# TFT_F1_2025-05-25_16-21-43.net
KiCad netlist of a schematic drawn in EasyEDA Pro
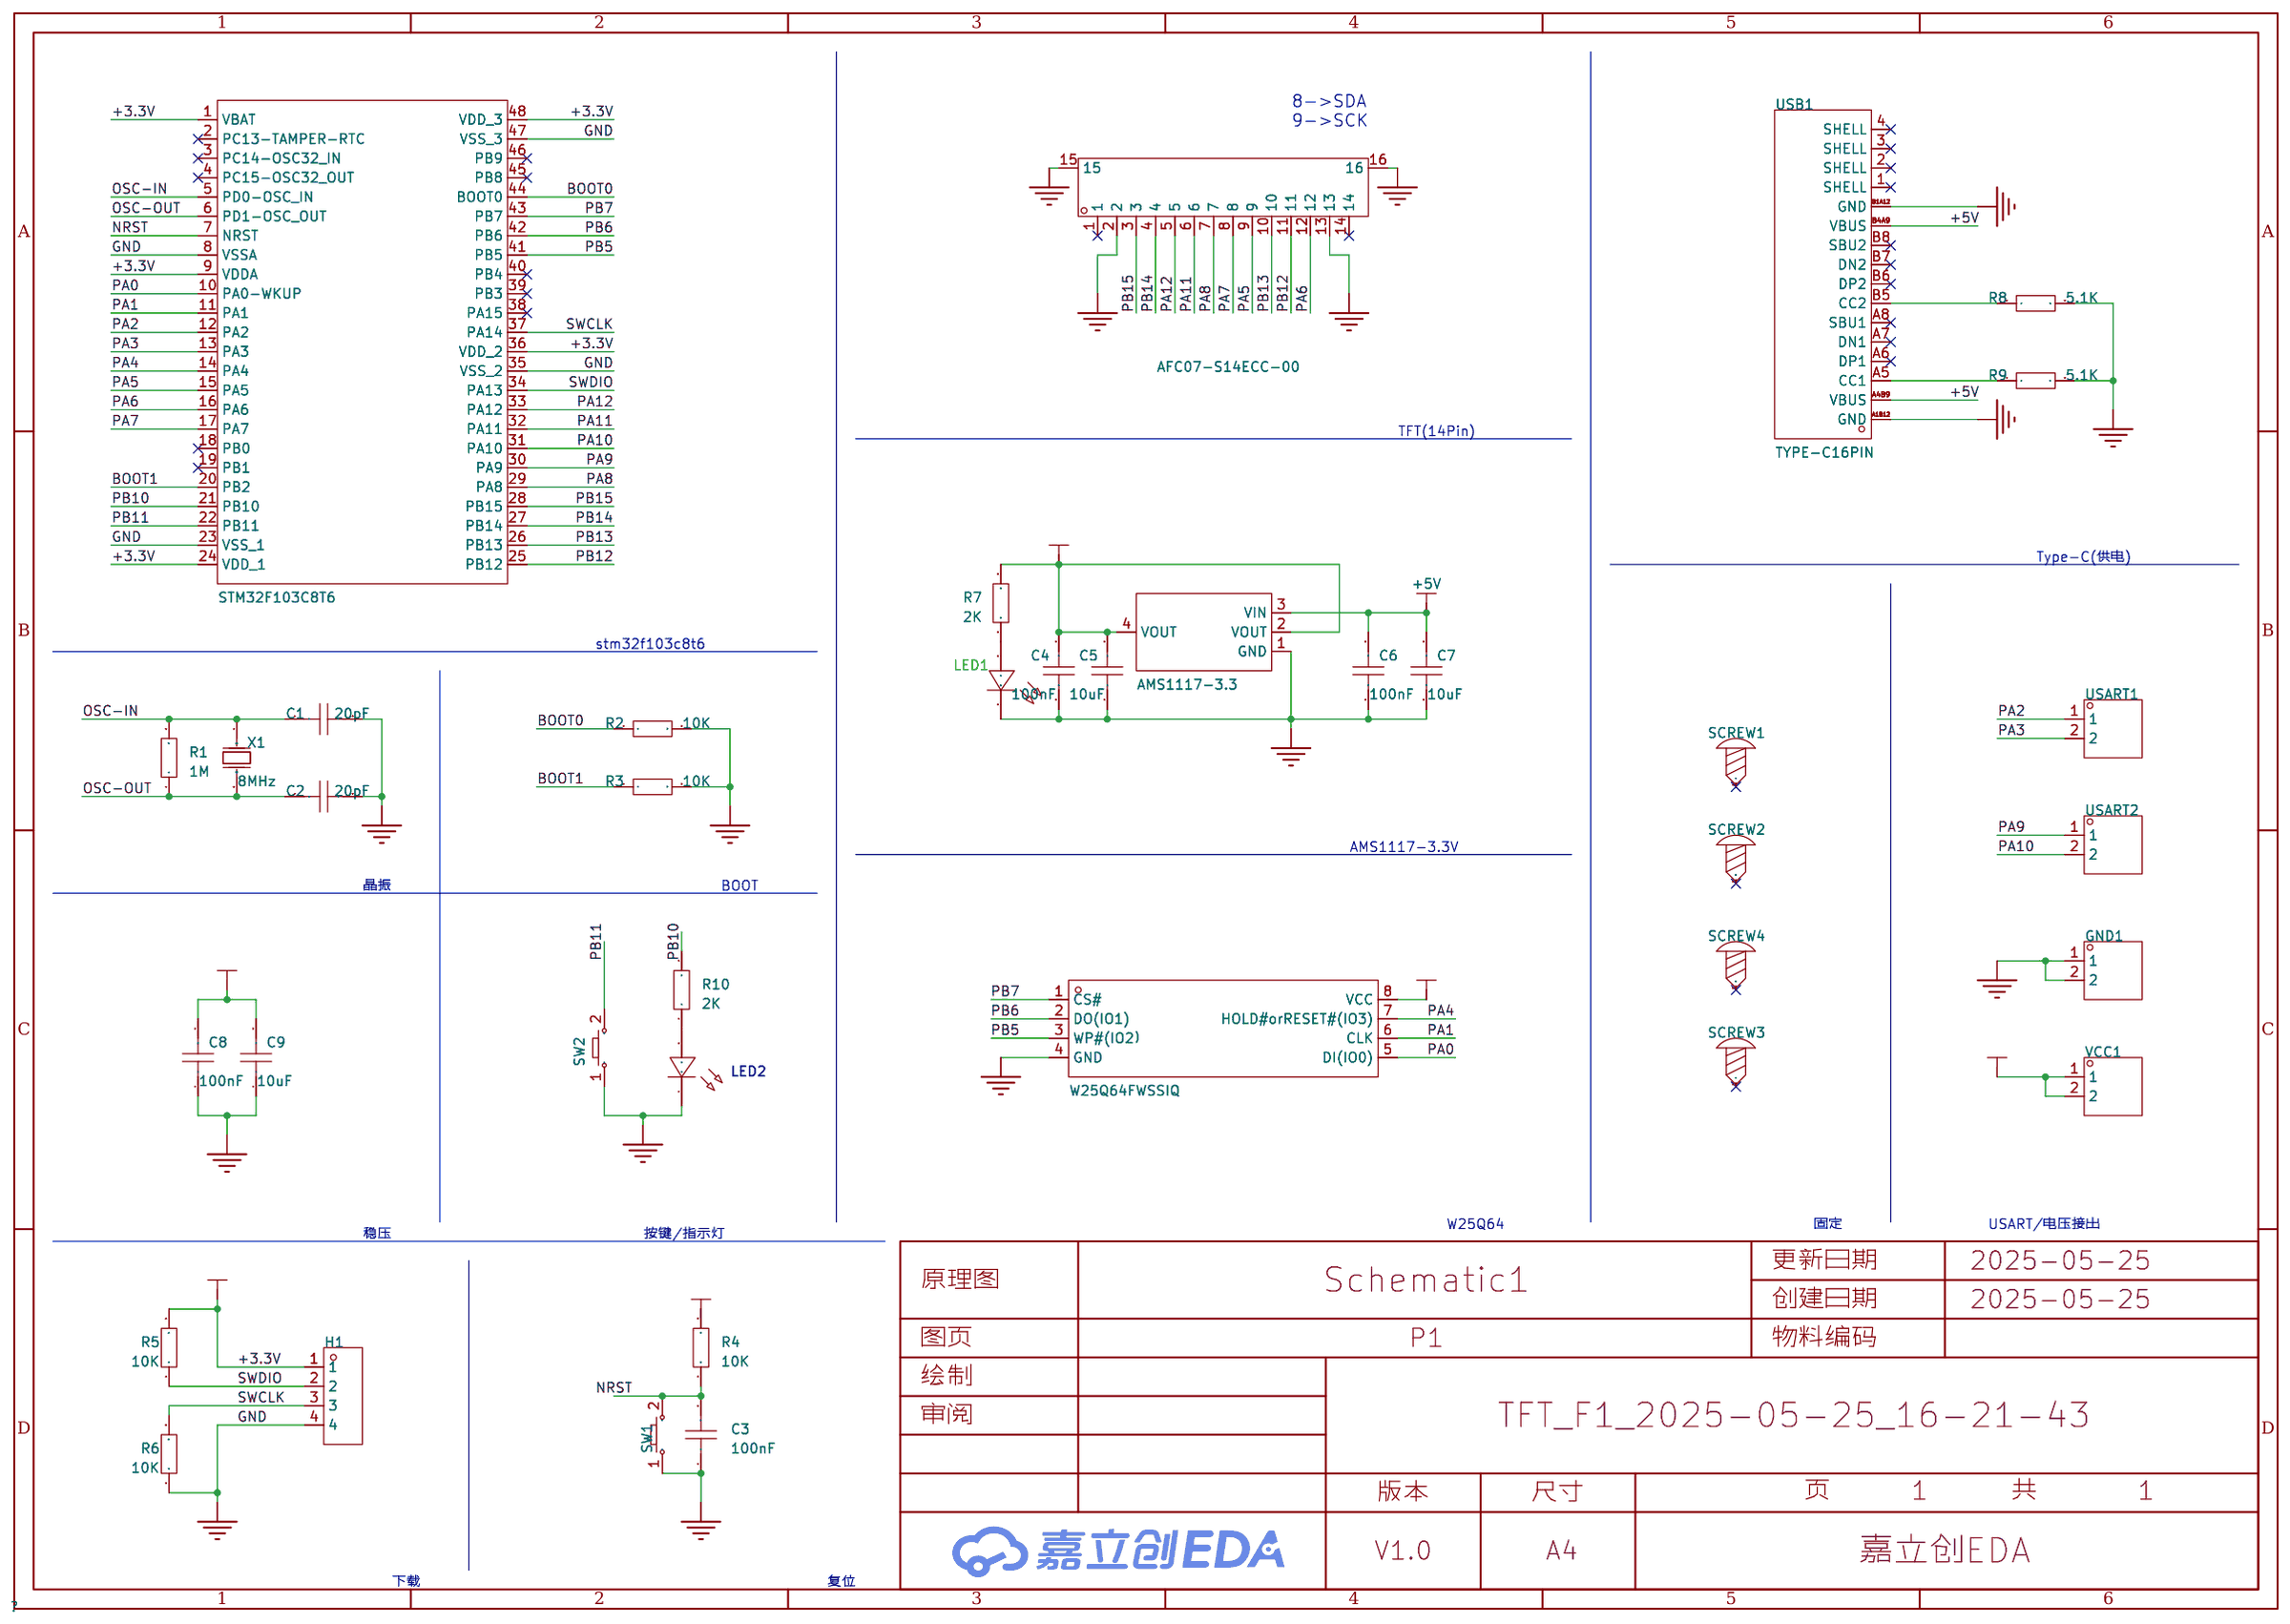
[diagram p0: schematic sheet]

(export (version "E")
  (design (tool "Eeschema 10.0.6"))
  (components
    (comp (ref "C1")
      (value "20pF")
      (footprint "easyedapro:C0805")
      (libsource (lib "easyedapro") (part "CapAcitance"))
    )
    (comp (ref "C2")
      (value "20pF")
      (footprint "easyedapro:C0805")
      (libsource (lib "easyedapro") (part "CapAcitance"))
    )
    (comp (ref "C3")
      (value "100nF")
      (footprint "easyedapro:C0805")
      (libsource (lib "easyedapro") (part "CapAcitance"))
    )
    (comp (ref "C4")
      (value "100nF")
      (footprint "easyedapro:C0805")
      (libsource (lib "easyedapro") (part "CapAcitance"))
    )
    (comp (ref "C5")
      (value "10uF")
      (footprint "easyedapro:C0805")
      (libsource (lib "easyedapro") (part "CapAcitance"))
    )
    (comp (ref "C6")
      (value "100nF")
      (footprint "easyedapro:C0805")
      (libsource (lib "easyedapro") (part "CapAcitance"))
    )
    (comp (ref "C7")
      (value "10uF")
      (footprint "easyedapro:C0805")
      (libsource (lib "easyedapro") (part "CapAcitance"))
    )
    (comp (ref "C8")
      (value "100nF")
      (footprint "easyedapro:C0805")
      (libsource (lib "easyedapro") (part "CapAcitance"))
    )
    (comp (ref "C9")
      (value "10uF")
      (footprint "easyedapro:C0805")
      (libsource (lib "easyedapro") (part "CapAcitance"))
    )
    (comp (ref "GND1")
      (value "~")
      (footprint "easyedapro:HDR-TH_2P-P2.54-V-M-1")
      (libsource (lib "easyedapro") (part "210S-1*2P L=11.6MMGold-plated black"))
    )
    (comp (ref "H1")
      (value "~")
      (footprint "easyedapro:HDR-TH_4P-P2.54-V-M")
      (libsource (lib "easyedapro") (part "PZ254V-11-04P"))
    )
    (comp (ref "LED1")
      (value "~")
      (footprint "easyedapro:LED_0805")
      (libsource (lib "easyedapro") (part "LED_G"))
    )
    (comp (ref "LED2")
      (value "~")
      (footprint "easyedapro:LED_0805")
      (libsource (lib "easyedapro") (part "LED_B"))
    )
    (comp (ref "P1")
      (value "AFC07-S14ECC-00")
      (footprint "easyedapro:FPC-SMD_14P-L12.5-W5.4-P0.50")
      (description "锁定特性:抽屉式;触点类型:上接;触点数量:14P;间距:0.5mm;安装类型:卧贴;")
      (fields (field (name "Manufacturer") "JS(钜硕电子)"))
      (libsource (lib "easyedapro") (part "FPC 0.5MM 14P Pull type H2.0mm Pick up"))
    )
    (comp (ref "R1") (value "1M") (footprint "easyedapro:R0805") (libsource (lib "easyedapro") (part "电阻")))
    (comp (ref "R2") (value "10K") (footprint "easyedapro:R0805") (libsource (lib "easyedapro") (part "电阻")))
    (comp (ref "R3") (value "10K") (footprint "easyedapro:R0805") (libsource (lib "easyedapro") (part "电阻")))
    (comp (ref "R4") (value "10K") (footprint "easyedapro:R0805") (libsource (lib "easyedapro") (part "电阻")))
    (comp (ref "R5") (value "10K") (footprint "easyedapro:R0805") (libsource (lib "easyedapro") (part "电阻")))
    (comp (ref "R6") (value "10K") (footprint "easyedapro:R0805") (libsource (lib "easyedapro") (part "电阻")))
    (comp (ref "R7") (value "2K") (footprint "easyedapro:R0805") (libsource (lib "easyedapro") (part "电阻")))
    (comp (ref "R8") (value "5.1K") (footprint "easyedapro:R0805") (libsource (lib "easyedapro") (part "电阻")))
    (comp (ref "R9") (value "5.1K") (footprint "easyedapro:R0805") (libsource (lib "easyedapro") (part "电阻")))
    (comp (ref "R10") (value "2K") (footprint "easyedapro:R0805") (libsource (lib "easyedapro") (part "电阻")))
    (comp (ref "SCREW1")
      (value "~")
      (footprint "easyedapro:M3螺丝")
      (libsource (lib "easyedapro") (part "螺丝孔"))
    )
    (comp (ref "SCREW2")
      (value "~")
      (footprint "easyedapro:M3螺丝")
      (libsource (lib "easyedapro") (part "螺丝孔"))
    )
    (comp (ref "SCREW3")
      (value "~")
      (footprint "easyedapro:M3螺丝")
      (libsource (lib "easyedapro") (part "螺丝孔"))
    )
    (comp (ref "SCREW4")
      (value "~")
      (footprint "easyedapro:M3螺丝")
      (libsource (lib "easyedapro") (part "螺丝孔"))
    )
    (comp (ref "SW1")
      (value "~")
      (footprint "easyedapro:Key_SMD_3x4x2")
      (libsource (lib "easyedapro") (part "轻触按键x2"))
    )
    (comp (ref "SW2")
      (value "~")
      (footprint "easyedapro:Key_SMD_3x4x2")
      (libsource (lib "easyedapro") (part "轻触按键x2"))
    )
    (comp (ref "U1")
      (value "STM32F103C8T6")
      (footprint "easyedapro:LQFP-48_L7.0-W7.0-P0.50-LS9.0-BL")
      (libsource (lib "easyedapro") (part "STM32F103C8T6_C9900100366"))
    )
    (comp (ref "U2")
      (value "AMS1117-3.3")
      (footprint "easyedapro:SOT-223-3_L6.5-W3.4-P2.30-LS7.0-BR")
      (description "输出类型:固定;工作电压:-;输出电压:3.3V;输出电流:1A;电源纹波抑制比(PSRR):72dB@(120Hz);输出极性:正极;")
      (fields (field (name "Manufacturer") "AMS"))
      (libsource (lib "easyedapro") (part "AMS1117-3.3"))
    )
    (comp (ref "U3")
      (value "W25Q64FWSSIQ")
      (footprint "easyedapro:SOIC-8_L5.3-W5.3-P1.27-LS8.0-BL")
      (fields (field (name "Manufacturer") "WINBOND(华邦)"))
      (libsource (lib "easyedapro") (part "W25Q64FWSSIQ"))
    )
    (comp (ref "USART1")
      (value "~")
      (footprint "easyedapro:HDR-TH_2P-P2.54-V-M-1")
      (libsource (lib "easyedapro") (part "210S-1*2P L=11.6MMGold-plated black"))
    )
    (comp (ref "USART2")
      (value "~")
      (footprint "easyedapro:HDR-TH_2P-P2.54-V-M-1")
      (libsource (lib "easyedapro") (part "210S-1*2P L=11.6MMGold-plated black"))
    )
    (comp (ref "USB1")
      (value "TYPE-C16PIN")
      (footprint "easyedapro:USB-C-SMD_TYPE-C16PIN")
      (description "连接器类型:Type-C;标准:USB 3.1;公母:母;安装方式:卧贴;触点数量:16P;端口数量:1;额定电流 - 电源:3A;工作温度范围:-40°C~+85°C;")
      (fields (field (name "Manufacturer") "SHOU HAN(首韩)"))
      (libsource (lib "easyedapro") (part "TYPE-C16PIN"))
    )
    (comp (ref "VCC1")
      (value "~")
      (footprint "easyedapro:HDR-TH_2P-P2.54-V-M-1")
      (libsource (lib "easyedapro") (part "210S-1*2P L=11.6MMGold-plated black"))
    )
    (comp (ref "X1")
      (value "8MHz")
      (footprint "easyedapro:CRYSTAL-SMD_L11.5-W4.8-LS12.7")
      (description "晶振类型:贴片晶振;频率:8MHz;常温频差:±20ppm;外接负载电容:20pF;频率稳定度(全温):±30ppm;")
      (fields (field (name "Manufacturer Part") "X49SM8MSD2SC") (field (name "Manufacturer") "YXC(扬兴晶振)"))
      (libsource (lib "easyedapro") (part "X49SM8MSD2SC"))
    )
  )
  (nets
    (net (code "1") (name "+3.3V") (class "Default")
      (node (ref "C4") (pin "2") (pinfunction "2_2") (pintype "input"))
      (node (ref "C5") (pin "2") (pinfunction "2_2") (pintype "input"))
      (node (ref "C8") (pin "2") (pinfunction "2_2") (pintype "input"))
      (node (ref "C9") (pin "2") (pinfunction "2_2") (pintype "input"))
      (node (ref "H1") (pin "1") (pinfunction "1_1") (pintype "unspecified"))
      (node (ref "R4") (pin "2") (pinfunction "2_2") (pintype "input"))
      (node (ref "R5") (pin "2") (pinfunction "2_2") (pintype "input"))
      (node (ref "R7") (pin "2") (pinfunction "2_2") (pintype "input"))
      (node (ref "U1") (pin "1") (pinfunction "VBAT_1") (pintype "unspecified"))
      (node (ref "U1") (pin "24") (pinfunction "VDD_1_24") (pintype "unspecified"))
      (node (ref "U1") (pin "36") (pinfunction "VDD_2_36") (pintype "unspecified"))
      (node (ref "U1") (pin "48") (pinfunction "VDD_3_48") (pintype "unspecified"))
      (node (ref "U1") (pin "9") (pinfunction "VDDA_9") (pintype "unspecified"))
      (node (ref "U2") (pin "2") (pinfunction "VOUT_2") (pintype "unspecified"))
      (node (ref "U2") (pin "4") (pinfunction "VOUT_4") (pintype "unspecified"))
      (node (ref "U3") (pin "8") (pinfunction "VCC_8") (pintype "unspecified"))
      (node (ref "VCC1") (pin "1") (pinfunction "1_1") (pintype "unspecified"))
      (node (ref "VCC1") (pin "2") (pinfunction "2_2") (pintype "unspecified"))
    )
    (net (code "2") (name "+5V") (class "Default")
      (node (ref "C6") (pin "2") (pinfunction "2_2") (pintype "input"))
      (node (ref "C7") (pin "2") (pinfunction "2_2") (pintype "input"))
      (node (ref "U2") (pin "3") (pinfunction "VIN_3") (pintype "unspecified"))
      (node (ref "USB1") (pin "A4B9") (pinfunction "VBUS_A4B9") (pintype "unspecified"))
      (node (ref "USB1") (pin "B4A9") (pinfunction "VBUS_B4A9") (pintype "unspecified"))
    )
    (net (code "3") (name "/BOOT0") (class "Default")
      (node (ref "R2") (pin "1") (pinfunction "1_1") (pintype "input"))
      (node (ref "U1") (pin "44") (pinfunction "BOOT0_44") (pintype "unspecified"))
    )
    (net (code "4") (name "/BOOT1") (class "Default")
      (node (ref "R3") (pin "1") (pinfunction "1_1") (pintype "input"))
      (node (ref "U1") (pin "20") (pinfunction "PB2_20") (pintype "unspecified"))
    )
    (net (code "5") (name "/NRST") (class "Default")
      (node (ref "C3") (pin "2") (pinfunction "2_2") (pintype "input"))
      (node (ref "R4") (pin "1") (pinfunction "1_1") (pintype "input"))
      (node (ref "SW1") (pin "2") (pinfunction "2_2") (pintype "input"))
      (node (ref "U1") (pin "7") (pinfunction "NRST_7") (pintype "unspecified"))
    )
    (net (code "6") (name "/OSC-IN") (class "Default")
      (node (ref "C1") (pin "1") (pinfunction "1_1") (pintype "input"))
      (node (ref "R1") (pin "2") (pinfunction "2_2") (pintype "input"))
      (node (ref "U1") (pin "5") (pinfunction "PD0-OSC_IN_5") (pintype "unspecified"))
      (node (ref "X1") (pin "1") (pinfunction "OSC1_1") (pintype "input"))
    )
    (net (code "7") (name "/OSC-OUT") (class "Default")
      (node (ref "C2") (pin "1") (pinfunction "1_1") (pintype "input"))
      (node (ref "R1") (pin "1") (pinfunction "1_1") (pintype "input"))
      (node (ref "U1") (pin "6") (pinfunction "PD1-OSC_OUT_6") (pintype "unspecified"))
      (node (ref "X1") (pin "2") (pinfunction "OSC2_2") (pintype "input"))
    )
    (net (code "8") (name "/PA0") (class "Default")
      (node (ref "U1") (pin "10") (pinfunction "PA0-WKUP_10") (pintype "unspecified"))
      (node (ref "U3") (pin "5") (pinfunction "DI(IO0)_5") (pintype "unspecified"))
    )
    (net (code "9") (name "/PA1") (class "Default")
      (node (ref "U1") (pin "11") (pinfunction "PA1_11") (pintype "unspecified"))
      (node (ref "U3") (pin "6") (pinfunction "CLK_6") (pintype "unspecified"))
    )
    (net (code "10") (name "/PA2") (class "Default")
      (node (ref "U1") (pin "12") (pinfunction "PA2_12") (pintype "unspecified"))
      (node (ref "USART1") (pin "1") (pinfunction "1_1") (pintype "unspecified"))
    )
    (net (code "11") (name "/PA3") (class "Default")
      (node (ref "U1") (pin "13") (pinfunction "PA3_13") (pintype "unspecified"))
      (node (ref "USART1") (pin "2") (pinfunction "2_2") (pintype "unspecified"))
    )
    (net (code "12") (name "/PA4") (class "Default")
      (node (ref "U1") (pin "14") (pinfunction "PA4_14") (pintype "unspecified"))
      (node (ref "U3") (pin "7") (pinfunction "HOLD#orRESET#(IO3)_7") (pintype "unspecified"))
    )
    (net (code "13") (name "/PA5") (class "Default")
      (node (ref "P1") (pin "9") (pinfunction "9_9") (pintype "unspecified"))
      (node (ref "U1") (pin "15") (pinfunction "PA5_15") (pintype "unspecified"))
    )
    (net (code "14") (name "/PA6") (class "Default")
      (node (ref "P1") (pin "12") (pinfunction "12_12") (pintype "unspecified"))
      (node (ref "U1") (pin "16") (pinfunction "PA6_16") (pintype "unspecified"))
    )
    (net (code "15") (name "/PA7") (class "Default")
      (node (ref "P1") (pin "8") (pinfunction "8_8") (pintype "unspecified"))
      (node (ref "U1") (pin "17") (pinfunction "PA7_17") (pintype "unspecified"))
    )
    (net (code "16") (name "/PA8") (class "Default")
      (node (ref "P1") (pin "7") (pinfunction "7_7") (pintype "unspecified"))
      (node (ref "U1") (pin "29") (pinfunction "PA8_29") (pintype "unspecified"))
    )
    (net (code "17") (name "/PA9") (class "Default")
      (node (ref "U1") (pin "30") (pinfunction "PA9_30") (pintype "unspecified"))
      (node (ref "USART2") (pin "1") (pinfunction "1_1") (pintype "unspecified"))
    )
    (net (code "18") (name "/PA10") (class "Default")
      (node (ref "U1") (pin "31") (pinfunction "PA10_31") (pintype "unspecified"))
      (node (ref "USART2") (pin "2") (pinfunction "2_2") (pintype "unspecified"))
    )
    (net (code "19") (name "/PA11") (class "Default")
      (node (ref "P1") (pin "6") (pinfunction "6_6") (pintype "unspecified"))
      (node (ref "U1") (pin "32") (pinfunction "PA11_32") (pintype "unspecified"))
    )
    (net (code "20") (name "/PA12") (class "Default")
      (node (ref "P1") (pin "5") (pinfunction "5_5") (pintype "unspecified"))
      (node (ref "U1") (pin "33") (pinfunction "PA12_33") (pintype "unspecified"))
    )
    (net (code "21") (name "/PB5") (class "Default")
      (node (ref "U1") (pin "41") (pinfunction "PB5_41") (pintype "unspecified"))
      (node (ref "U3") (pin "3") (pinfunction "WP#(IO2）_3") (pintype "unspecified"))
    )
    (net (code "22") (name "/PB6") (class "Default")
      (node (ref "U1") (pin "42") (pinfunction "PB6_42") (pintype "unspecified"))
      (node (ref "U3") (pin "2") (pinfunction "DO(IO1)_2") (pintype "unspecified"))
    )
    (net (code "23") (name "/PB7") (class "Default")
      (node (ref "U1") (pin "43") (pinfunction "PB7_43") (pintype "unspecified"))
      (node (ref "U3") (pin "1") (pinfunction "CS#_1") (pintype "unspecified"))
    )
    (net (code "24") (name "/PB10") (class "Default")
      (node (ref "R10") (pin "2") (pinfunction "2_2") (pintype "input"))
      (node (ref "U1") (pin "21") (pinfunction "PB10_21") (pintype "unspecified"))
    )
    (net (code "25") (name "/PB11") (class "Default")
      (node (ref "SW2") (pin "2") (pinfunction "2_2") (pintype "input"))
      (node (ref "U1") (pin "22") (pinfunction "PB11_22") (pintype "unspecified"))
    )
    (net (code "26") (name "/PB12") (class "Default")
      (node (ref "P1") (pin "11") (pinfunction "11_11") (pintype "unspecified"))
      (node (ref "U1") (pin "25") (pinfunction "PB12_25") (pintype "unspecified"))
    )
    (net (code "27") (name "/PB13") (class "Default")
      (node (ref "P1") (pin "10") (pinfunction "10_10") (pintype "unspecified"))
      (node (ref "U1") (pin "26") (pinfunction "PB13_26") (pintype "unspecified"))
    )
    (net (code "28") (name "/PB14") (class "Default")
      (node (ref "P1") (pin "4") (pinfunction "4_4") (pintype "unspecified"))
      (node (ref "U1") (pin "27") (pinfunction "PB14_27") (pintype "unspecified"))
    )
    (net (code "29") (name "/PB15") (class "Default")
      (node (ref "P1") (pin "3") (pinfunction "3_3") (pintype "unspecified"))
      (node (ref "U1") (pin "28") (pinfunction "PB15_28") (pintype "unspecified"))
    )
    (net (code "30") (name "/SWCLK") (class "Default")
      (node (ref "H1") (pin "3") (pinfunction "3_3") (pintype "unspecified"))
      (node (ref "R6") (pin "2") (pinfunction "2_2") (pintype "input"))
      (node (ref "U1") (pin "37") (pinfunction "PA14_37") (pintype "unspecified"))
    )
    (net (code "31") (name "/SWDIO") (class "Default")
      (node (ref "H1") (pin "2") (pinfunction "2_2") (pintype "unspecified"))
      (node (ref "R5") (pin "1") (pinfunction "1_1") (pintype "input"))
      (node (ref "U1") (pin "34") (pinfunction "PA13_34") (pintype "unspecified"))
    )
    (net (code "32") (name "GND") (class "Default")
      (node (ref "C1") (pin "2") (pinfunction "2_2") (pintype "input"))
      (node (ref "C2") (pin "2") (pinfunction "2_2") (pintype "input"))
      (node (ref "C3") (pin "1") (pinfunction "1_1") (pintype "input"))
      (node (ref "C4") (pin "1") (pinfunction "1_1") (pintype "input"))
      (node (ref "C5") (pin "1") (pinfunction "1_1") (pintype "input"))
      (node (ref "C6") (pin "1") (pinfunction "1_1") (pintype "input"))
      (node (ref "C7") (pin "1") (pinfunction "1_1") (pintype "input"))
      (node (ref "C8") (pin "1") (pinfunction "1_1") (pintype "input"))
      (node (ref "C9") (pin "1") (pinfunction "1_1") (pintype "input"))
      (node (ref "GND1") (pin "1") (pinfunction "1_1") (pintype "unspecified"))
      (node (ref "GND1") (pin "2") (pinfunction "2_2") (pintype "unspecified"))
      (node (ref "H1") (pin "4") (pinfunction "4_4") (pintype "unspecified"))
      (node (ref "LED1") (pin "1") (pinfunction "C_1") (pintype "input"))
      (node (ref "LED2") (pin "1") (pinfunction "C_1") (pintype "input"))
      (node (ref "P1") (pin "13") (pinfunction "13_13") (pintype "unspecified"))
      (node (ref "P1") (pin "15") (pinfunction "15_15") (pintype "unspecified"))
      (node (ref "P1") (pin "16") (pinfunction "16_16") (pintype "unspecified"))
      (node (ref "P1") (pin "2") (pinfunction "2_2") (pintype "unspecified"))
      (node (ref "R2") (pin "2") (pinfunction "2_2") (pintype "input"))
      (node (ref "R3") (pin "2") (pinfunction "2_2") (pintype "input"))
      (node (ref "R6") (pin "1") (pinfunction "1_1") (pintype "input"))
      (node (ref "R8") (pin "2") (pinfunction "2_2") (pintype "input"))
      (node (ref "R9") (pin "2") (pinfunction "2_2") (pintype "input"))
      (node (ref "SW1") (pin "1") (pinfunction "1_1") (pintype "input"))
      (node (ref "SW2") (pin "1") (pinfunction "1_1") (pintype "input"))
      (node (ref "U1") (pin "23") (pinfunction "VSS_1_23") (pintype "unspecified"))
      (node (ref "U1") (pin "35") (pinfunction "VSS_2_35") (pintype "unspecified"))
      (node (ref "U1") (pin "47") (pinfunction "VSS_3_47") (pintype "unspecified"))
      (node (ref "U1") (pin "8") (pinfunction "VSSA_8") (pintype "unspecified"))
      (node (ref "U2") (pin "1") (pinfunction "GND_1") (pintype "unspecified"))
      (node (ref "U3") (pin "4") (pinfunction "GND_4") (pintype "unspecified"))
      (node (ref "USB1") (pin "A1B12") (pinfunction "GND_A1B12") (pintype "unspecified"))
      (node (ref "USB1") (pin "B1A12") (pinfunction "GND_B1A12") (pintype "unspecified"))
    )
    (net (code "33") (name "Net-(LED1-A)") (class "Default")
      (node (ref "LED1") (pin "2") (pinfunction "A_2") (pintype "input"))
      (node (ref "R7") (pin "1") (pinfunction "1_1") (pintype "input"))
    )
    (net (code "34") (name "Net-(LED2-A)") (class "Default")
      (node (ref "LED2") (pin "2") (pinfunction "A_2") (pintype "input"))
      (node (ref "R10") (pin "1") (pinfunction "1_1") (pintype "input"))
    )
    (net (code "35") (name "Net-(USB1-CC1)") (class "Default")
      (node (ref "R9") (pin "1") (pinfunction "1_1") (pintype "input"))
      (node (ref "USB1") (pin "A5") (pinfunction "CC1_A5") (pintype "unspecified"))
    )
    (net (code "36") (name "Net-(USB1-CC2)") (class "Default")
      (node (ref "R8") (pin "1") (pinfunction "1_1") (pintype "input"))
      (node (ref "USB1") (pin "B5") (pinfunction "CC2_B5") (pintype "unspecified"))
    )
    (net (code "37") (name "unconnected-(P1-Pad1)") (class "Default")
      (node (ref "P1") (pin "1") (pinfunction "1_1") (pintype "unspecified+no_connect"))
    )
    (net (code "38") (name "unconnected-(P1-Pad14)") (class "Default")
      (node (ref "P1") (pin "14") (pinfunction "14_14") (pintype "unspecified+no_connect"))
    )
    (net (code "39") (name "unconnected-(SCREW1-Pad1)") (class "Default")
      (node (ref "SCREW1") (pin "1") (pinfunction "1_1") (pintype "input+no_connect"))
    )
    (net (code "40") (name "unconnected-(SCREW2-Pad1)") (class "Default")
      (node (ref "SCREW2") (pin "1") (pinfunction "1_1") (pintype "input+no_connect"))
    )
    (net (code "41") (name "unconnected-(SCREW3-Pad1)") (class "Default")
      (node (ref "SCREW3") (pin "1") (pinfunction "1_1") (pintype "input+no_connect"))
    )
    (net (code "42") (name "unconnected-(SCREW4-Pad1)") (class "Default")
      (node (ref "SCREW4") (pin "1") (pinfunction "1_1") (pintype "input+no_connect"))
    )
    (net (code "43") (name "unconnected-(U1-PA15-Pad38)") (class "Default")
      (node (ref "U1") (pin "38") (pinfunction "PA15_38") (pintype "unspecified+no_connect"))
    )
    (net (code "44") (name "unconnected-(U1-PB0-Pad18)") (class "Default")
      (node (ref "U1") (pin "18") (pinfunction "PB0_18") (pintype "unspecified+no_connect"))
    )
    (net (code "45") (name "unconnected-(U1-PB1-Pad19)") (class "Default")
      (node (ref "U1") (pin "19") (pinfunction "PB1_19") (pintype "unspecified+no_connect"))
    )
    (net (code "46") (name "unconnected-(U1-PB3-Pad39)") (class "Default")
      (node (ref "U1") (pin "39") (pinfunction "PB3_39") (pintype "unspecified+no_connect"))
    )
    (net (code "47") (name "unconnected-(U1-PB4-Pad40)") (class "Default")
      (node (ref "U1") (pin "40") (pinfunction "PB4_40") (pintype "unspecified+no_connect"))
    )
    (net (code "48") (name "unconnected-(U1-PB8-Pad45)") (class "Default")
      (node (ref "U1") (pin "45") (pinfunction "PB8_45") (pintype "unspecified+no_connect"))
    )
    (net (code "49") (name "unconnected-(U1-PB9-Pad46)") (class "Default")
      (node (ref "U1") (pin "46") (pinfunction "PB9_46") (pintype "unspecified+no_connect"))
    )
    (net (code "50") (name "unconnected-(U1-PC13-TAMPER-RTC-Pad2)") (class "Default")
      (node (ref "U1") (pin "2") (pinfunction "PC13-TAMPER-RTC_2") (pintype "unspecified+no_connect"))
    )
    (net (code "51") (name "unconnected-(U1-PC14-OSC32_IN-Pad3)") (class "Default")
      (node (ref "U1") (pin "3") (pinfunction "PC14-OSC32_IN_3") (pintype "unspecified+no_connect"))
    )
    (net (code "52") (name "unconnected-(U1-PC15-OSC32_OUT-Pad4)") (class "Default")
      (node (ref "U1") (pin "4") (pinfunction "PC15-OSC32_OUT_4") (pintype "unspecified+no_connect"))
    )
    (net (code "53") (name "unconnected-(USB1-DN1-PadA7)") (class "Default")
      (node (ref "USB1") (pin "A7") (pinfunction "DN1_A7") (pintype "unspecified+no_connect"))
    )
    (net (code "54") (name "unconnected-(USB1-DN2-PadB7)") (class "Default")
      (node (ref "USB1") (pin "B7") (pinfunction "DN2_B7") (pintype "unspecified+no_connect"))
    )
    (net (code "55") (name "unconnected-(USB1-DP1-PadA6)") (class "Default")
      (node (ref "USB1") (pin "A6") (pinfunction "DP1_A6") (pintype "unspecified+no_connect"))
    )
    (net (code "56") (name "unconnected-(USB1-DP2-PadB6)") (class "Default")
      (node (ref "USB1") (pin "B6") (pinfunction "DP2_B6") (pintype "unspecified+no_connect"))
    )
    (net (code "57") (name "unconnected-(USB1-SBU1-PadA8)") (class "Default")
      (node (ref "USB1") (pin "A8") (pinfunction "SBU1_A8") (pintype "unspecified+no_connect"))
    )
    (net (code "58") (name "unconnected-(USB1-SBU2-PadB8)") (class "Default")
      (node (ref "USB1") (pin "B8") (pinfunction "SBU2_B8") (pintype "unspecified+no_connect"))
    )
    (net (code "59") (name "unconnected-(USB1-SHELL-Pad1)") (class "Default")
      (node (ref "USB1") (pin "1") (pinfunction "SHELL_1") (pintype "unspecified+no_connect"))
    )
    (net (code "60") (name "unconnected-(USB1-SHELL-Pad2)") (class "Default")
      (node (ref "USB1") (pin "2") (pinfunction "SHELL_2") (pintype "unspecified+no_connect"))
    )
    (net (code "61") (name "unconnected-(USB1-SHELL-Pad3)") (class "Default")
      (node (ref "USB1") (pin "3") (pinfunction "SHELL_3") (pintype "unspecified+no_connect"))
    )
    (net (code "62") (name "unconnected-(USB1-SHELL-Pad4)") (class "Default")
      (node (ref "USB1") (pin "4") (pinfunction "SHELL_4") (pintype "unspecified+no_connect"))
    )
  )
)
